# analogue-board.net
KiCad netlist of a schematic drawn in EAGLE
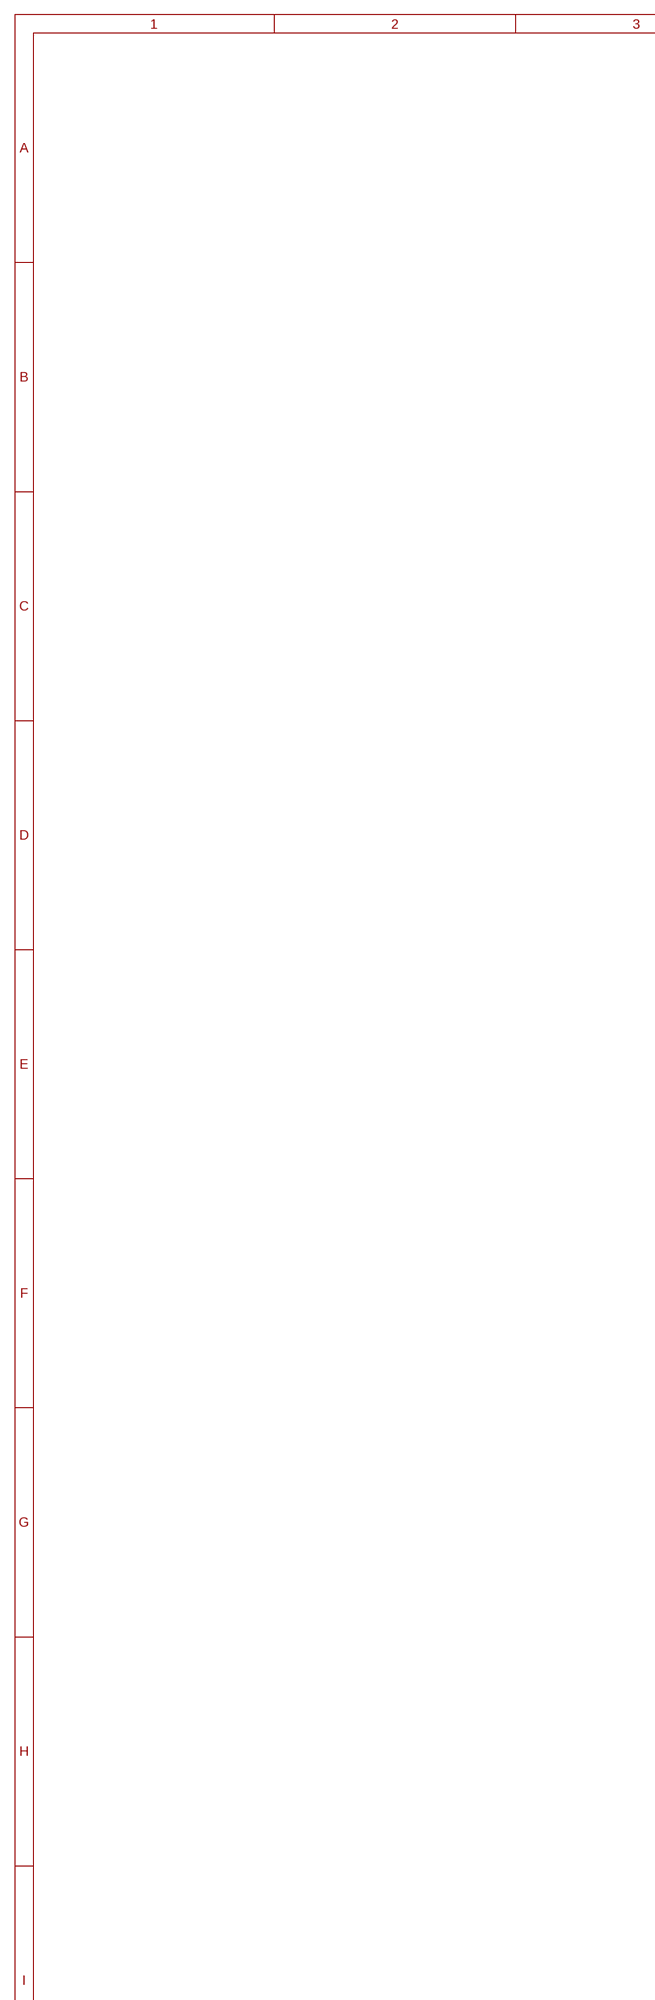
[diagram p0: schematic, sheet 1, part 1 of 2]
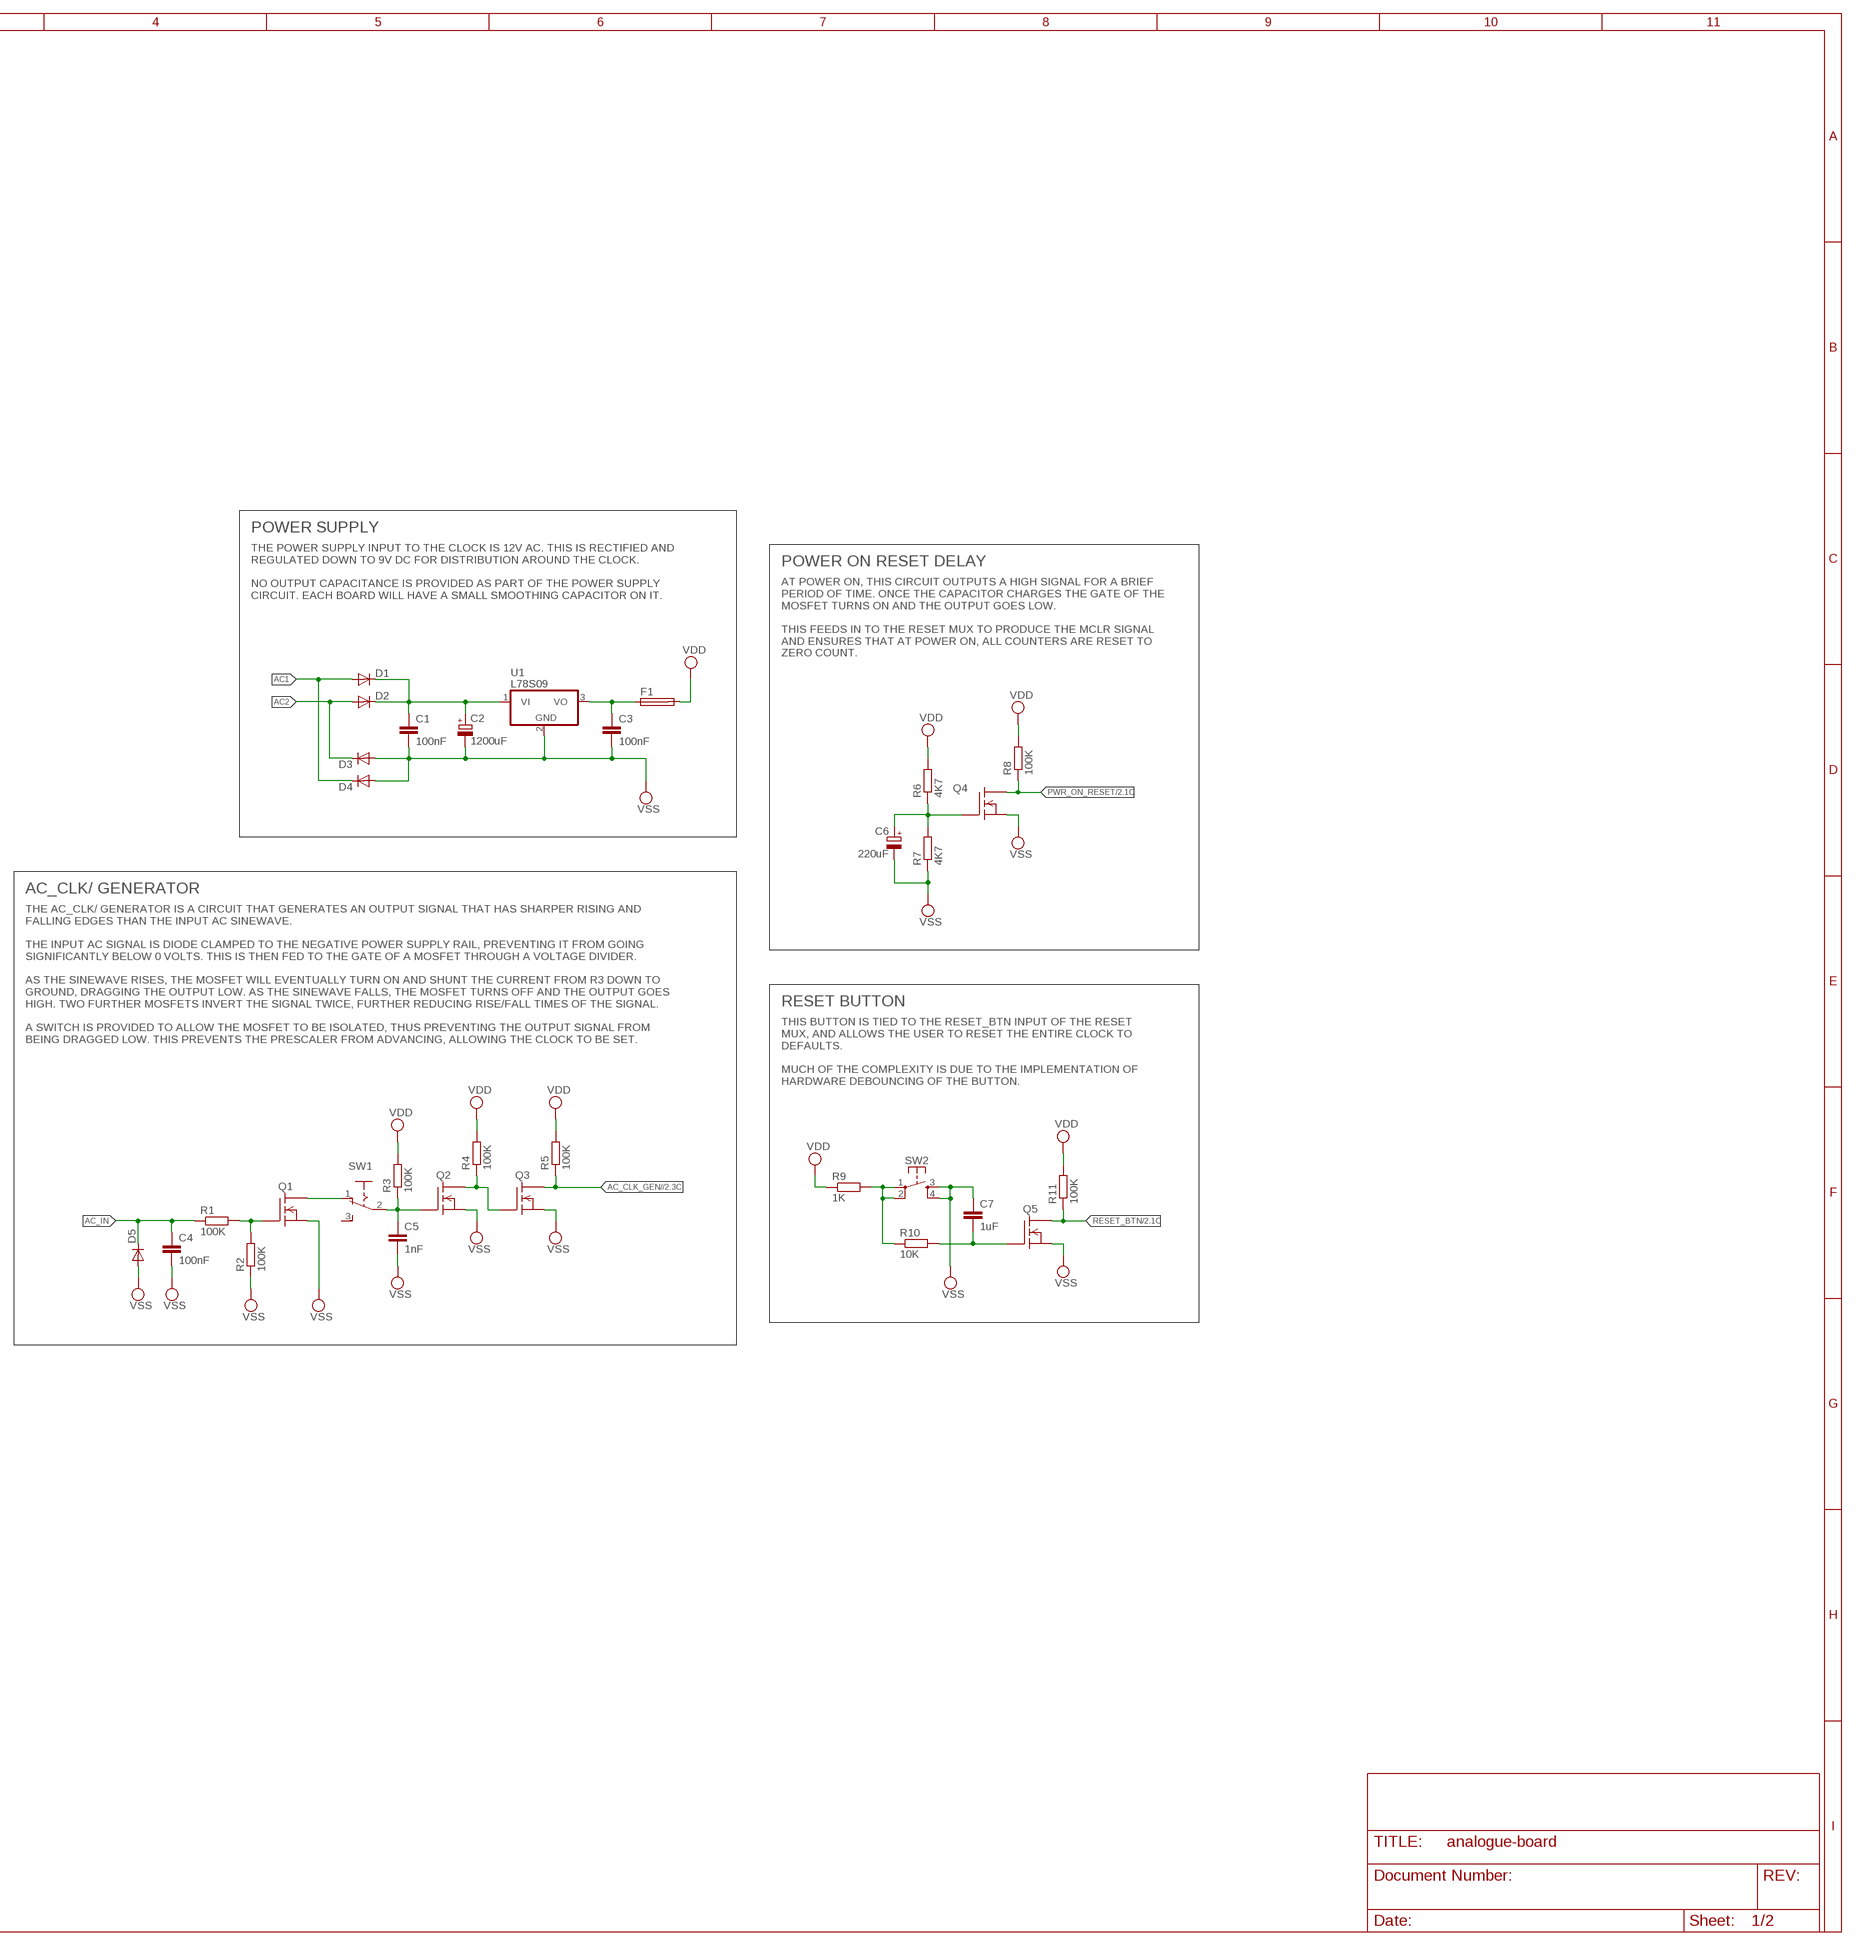
[diagram p1: schematic, sheet 1, part 2 of 2]
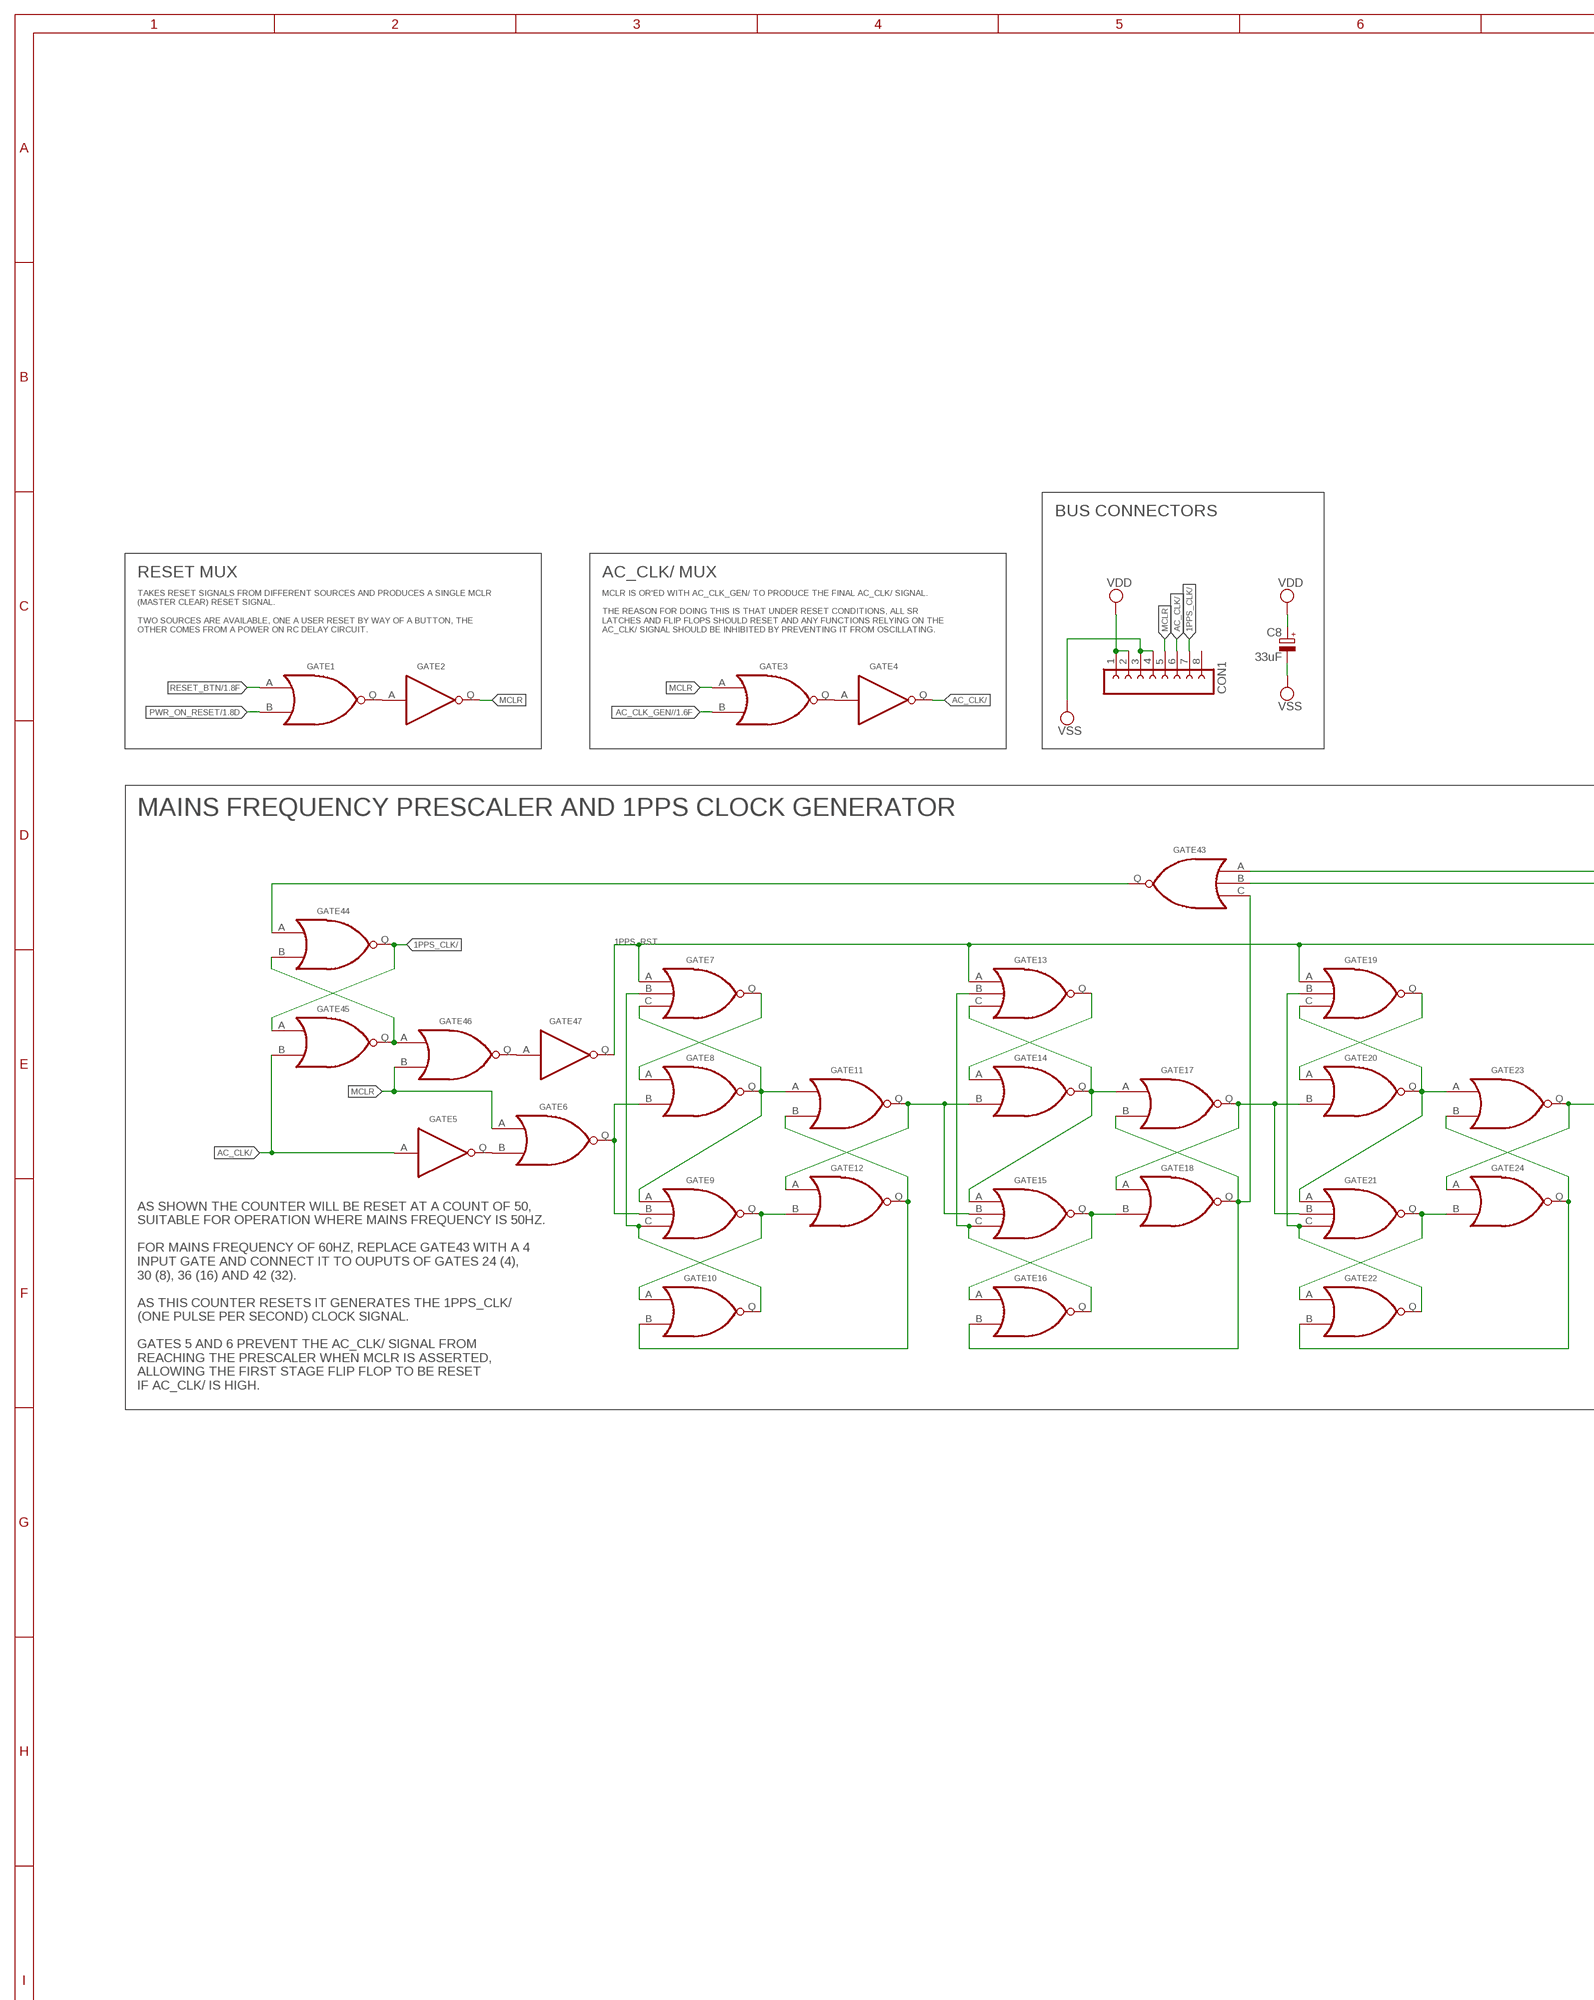
[diagram p2: schematic, sheet 2, part 1 of 2]
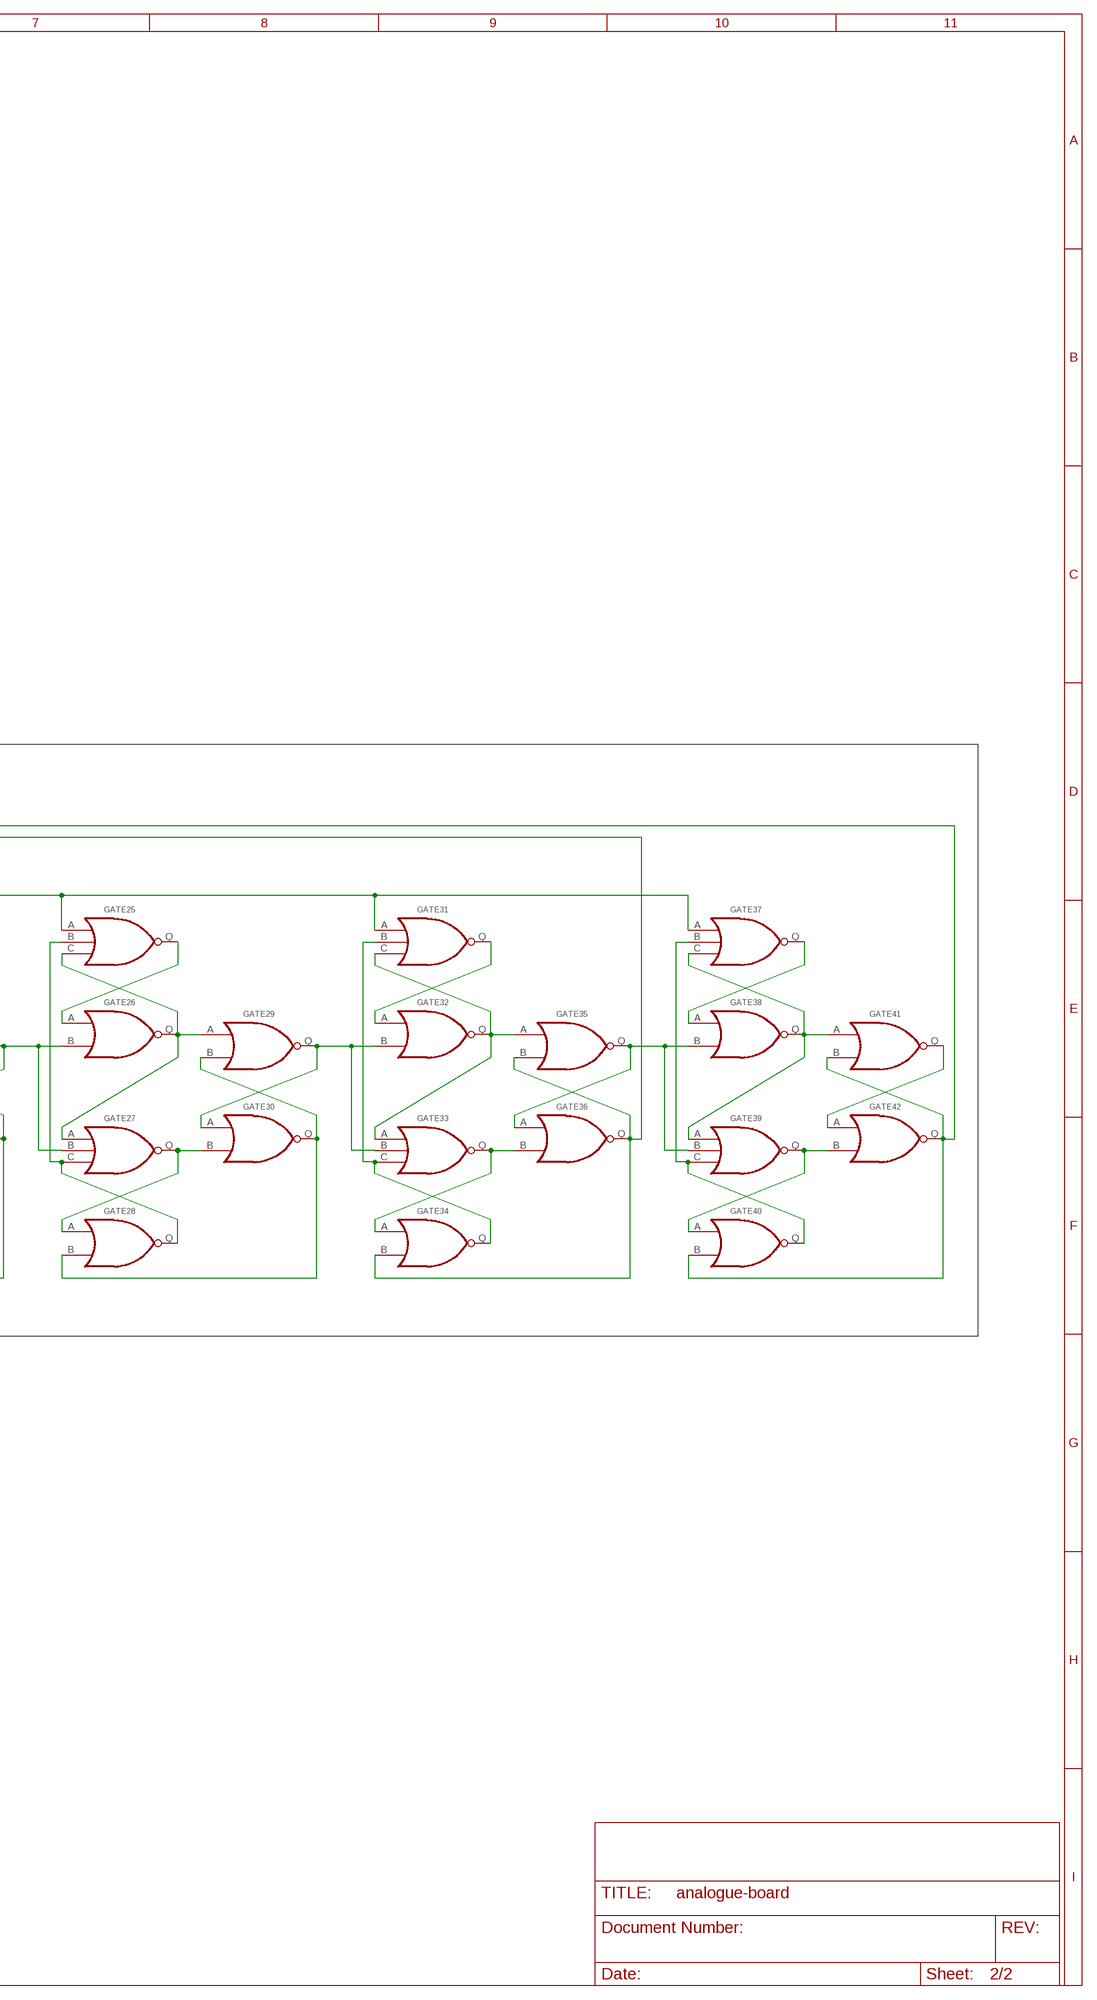
[diagram p3: schematic, sheet 2, part 2 of 2]

(export (version "E")
  (design (tool "Eeschema 10.0.6"))
  (components
    (comp (ref "C1")
      (value "100nF")
      (footprint "eagle-import:C050-024X044")
      (libsource (lib "eagle-import") (part "C-EU050-024X044"))
    )
    (comp (ref "C2")
      (value "1200uF")
      (footprint "eagle-import:E7,5-16")
      (libsource (lib "eagle-import") (part "CPOL-EUE7.5-16"))
    )
    (comp (ref "C3")
      (value "100nF")
      (footprint "eagle-import:C050-024X044")
      (libsource (lib "eagle-import") (part "C-EU050-024X044"))
    )
    (comp (ref "C4")
      (value "100nF")
      (footprint "eagle-import:C050-024X044")
      (libsource (lib "eagle-import") (part "C-EU050-024X044"))
    )
    (comp (ref "C5")
      (value "1nF")
      (footprint "eagle-import:C050-025X075")
      (libsource (lib "eagle-import") (part "C-EU050-025X075"))
    )
    (comp (ref "C6")
      (value "220uF")
      (footprint "eagle-import:E2,5-6")
      (libsource (lib "eagle-import") (part "CPOL-EUE2.5-6"))
    )
    (comp (ref "C7")
      (value "1uF")
      (footprint "eagle-import:C050-025X075")
      (libsource (lib "eagle-import") (part "C-EU050-025X075"))
    )
    (comp (ref "D1")
      (value "1N4004")
      (footprint "eagle-import:DO41-10")
      (libsource (lib "eagle-import") (part "1N4004"))
    )
    (comp (ref "D2")
      (value "1N4004")
      (footprint "eagle-import:DO41-10")
      (libsource (lib "eagle-import") (part "1N4004"))
    )
    (comp (ref "D3")
      (value "1N4004")
      (footprint "eagle-import:DO41-10")
      (libsource (lib "eagle-import") (part "1N4004"))
    )
    (comp (ref "D4")
      (value "1N4004")
      (footprint "eagle-import:DO41-10")
      (libsource (lib "eagle-import") (part "1N4004"))
    )
    (comp (ref "D5")
      (value "1N4004")
      (footprint "eagle-import:DO41-10")
      (libsource (lib "eagle-import") (part "1N4004"))
    )
    (comp (ref "F1")
      (value "TE5")
      (footprint "eagle-import:TE5")
      (libsource (lib "eagle-import") (part "TE5"))
    )
    (comp (ref "Q1")
      (value "2N7000")
      (footprint "eagle-import:TO-92")
      (libsource (lib "eagle-import") (part "2N7000"))
    )
    (comp (ref "Q2")
      (value "2N7000")
      (footprint "eagle-import:TO-92")
      (libsource (lib "eagle-import") (part "2N7000"))
    )
    (comp (ref "Q3")
      (value "2N7000")
      (footprint "eagle-import:TO-92")
      (libsource (lib "eagle-import") (part "2N7000"))
    )
    (comp (ref "Q4")
      (value "2N7000")
      (footprint "eagle-import:TO-92")
      (libsource (lib "eagle-import") (part "2N7000"))
    )
    (comp (ref "Q5")
      (value "2N7000")
      (footprint "eagle-import:TO-92")
      (libsource (lib "eagle-import") (part "2N7000"))
    )
    (comp (ref "R1")
      (value "100K")
      (footprint "eagle-import:0207_2V")
      (libsource (lib "eagle-import") (part "R-EU_0207/2V"))
    )
    (comp (ref "R2")
      (value "100K")
      (footprint "eagle-import:0207_2V")
      (libsource (lib "eagle-import") (part "R-EU_0207/2V"))
    )
    (comp (ref "R3")
      (value "100K")
      (footprint "eagle-import:0207_2V")
      (libsource (lib "eagle-import") (part "R-EU_0207/2V"))
    )
    (comp (ref "R4")
      (value "100K")
      (footprint "eagle-import:0207_2V")
      (libsource (lib "eagle-import") (part "R-EU_0207/2V"))
    )
    (comp (ref "R5")
      (value "100K")
      (footprint "eagle-import:0207_2V")
      (libsource (lib "eagle-import") (part "R-EU_0207/2V"))
    )
    (comp (ref "R6")
      (value "4K7")
      (footprint "eagle-import:0207_2V")
      (libsource (lib "eagle-import") (part "R-EU_0207/2V"))
    )
    (comp (ref "R7")
      (value "4K7")
      (footprint "eagle-import:0207_2V")
      (libsource (lib "eagle-import") (part "R-EU_0207/2V"))
    )
    (comp (ref "R8")
      (value "100K")
      (footprint "eagle-import:0207_2V")
      (libsource (lib "eagle-import") (part "R-EU_0207/2V"))
    )
    (comp (ref "R9")
      (value "1K")
      (footprint "eagle-import:0207_2V")
      (libsource (lib "eagle-import") (part "R-EU_0207/2V"))
    )
    (comp (ref "R10")
      (value "10K")
      (footprint "eagle-import:0207_2V")
      (libsource (lib "eagle-import") (part "R-EU_0207/2V"))
    )
    (comp (ref "R11")
      (value "100K")
      (footprint "eagle-import:0207_2V")
      (libsource (lib "eagle-import") (part "R-EU_0207/2V"))
    )
    (comp (ref "SW1")
      (value "255SB")
      (footprint "eagle-import:255SB")
      (libsource (lib "eagle-import") (part "255SB"))
    )
    (comp (ref "SW2")
      (value "SPST-TACSWITCH")
      (footprint "eagle-import:TE-SMD-TACSWITCH")
      (libsource (lib "eagle-import") (part "SPST-TACSWITCH"))
    )
    (comp (ref "U1")
      (value "L78S09")
      (footprint "eagle-import:TO220H")
      (libsource (lib "eagle-import") (part "78T05"))
    )
    (comp (ref "C8")
      (value "33uF")
      (footprint "eagle-import:E2,5-6")
      (libsource (lib "eagle-import") (part "CPOL-EUE2.5-6"))
    )
    (comp (ref "CON1")
      (value "FE08-1")
      (footprint "eagle-import:FE08")
      (libsource (lib "eagle-import") (part "FE08-1"))
    )
    (comp (ref "GATE1")
      (value "2NOR")
      (footprint "eagle-import:2NOR")
      (libsource (lib "eagle-import") (part "2NOR"))
    )
    (comp (ref "GATE2")
      (value "INVERTER")
      (footprint "eagle-import:INVERTER")
      (libsource (lib "eagle-import") (part "INVERTER"))
    )
    (comp (ref "GATE3")
      (value "2NOR")
      (footprint "eagle-import:2NOR")
      (libsource (lib "eagle-import") (part "2NOR"))
    )
    (comp (ref "GATE4")
      (value "INVERTER")
      (footprint "eagle-import:INVERTER")
      (libsource (lib "eagle-import") (part "INVERTER"))
    )
    (comp (ref "GATE5")
      (value "INVERTER")
      (footprint "eagle-import:INVERTER")
      (libsource (lib "eagle-import") (part "INVERTER"))
    )
    (comp (ref "GATE6")
      (value "2NOR")
      (footprint "eagle-import:2NOR")
      (libsource (lib "eagle-import") (part "2NOR"))
    )
    (comp (ref "GATE7")
      (value "3NOR")
      (footprint "eagle-import:3NOR")
      (libsource (lib "eagle-import") (part "3NOR"))
    )
    (comp (ref "GATE8")
      (value "2NOR")
      (footprint "eagle-import:2NOR")
      (libsource (lib "eagle-import") (part "2NOR"))
    )
    (comp (ref "GATE9")
      (value "3NOR")
      (footprint "eagle-import:3NOR")
      (libsource (lib "eagle-import") (part "3NOR"))
    )
    (comp (ref "GATE10")
      (value "2NOR")
      (footprint "eagle-import:2NOR")
      (libsource (lib "eagle-import") (part "2NOR"))
    )
    (comp (ref "GATE11")
      (value "2NOR")
      (footprint "eagle-import:2NOR")
      (libsource (lib "eagle-import") (part "2NOR"))
    )
    (comp (ref "GATE12")
      (value "2NOR")
      (footprint "eagle-import:2NOR")
      (libsource (lib "eagle-import") (part "2NOR"))
    )
    (comp (ref "GATE13")
      (value "3NOR")
      (footprint "eagle-import:3NOR")
      (libsource (lib "eagle-import") (part "3NOR"))
    )
    (comp (ref "GATE14")
      (value "2NOR")
      (footprint "eagle-import:2NOR")
      (libsource (lib "eagle-import") (part "2NOR"))
    )
    (comp (ref "GATE15")
      (value "3NOR")
      (footprint "eagle-import:3NOR")
      (libsource (lib "eagle-import") (part "3NOR"))
    )
    (comp (ref "GATE16")
      (value "2NOR")
      (footprint "eagle-import:2NOR")
      (libsource (lib "eagle-import") (part "2NOR"))
    )
    (comp (ref "GATE17")
      (value "2NOR")
      (footprint "eagle-import:2NOR")
      (libsource (lib "eagle-import") (part "2NOR"))
    )
    (comp (ref "GATE18")
      (value "2NOR")
      (footprint "eagle-import:2NOR")
      (libsource (lib "eagle-import") (part "2NOR"))
    )
    (comp (ref "GATE19")
      (value "3NOR")
      (footprint "eagle-import:3NOR")
      (libsource (lib "eagle-import") (part "3NOR"))
    )
    (comp (ref "GATE20")
      (value "2NOR")
      (footprint "eagle-import:2NOR")
      (libsource (lib "eagle-import") (part "2NOR"))
    )
    (comp (ref "GATE21")
      (value "3NOR")
      (footprint "eagle-import:3NOR")
      (libsource (lib "eagle-import") (part "3NOR"))
    )
    (comp (ref "GATE22")
      (value "2NOR")
      (footprint "eagle-import:2NOR")
      (libsource (lib "eagle-import") (part "2NOR"))
    )
    (comp (ref "GATE23")
      (value "2NOR")
      (footprint "eagle-import:2NOR")
      (libsource (lib "eagle-import") (part "2NOR"))
    )
    (comp (ref "GATE24")
      (value "2NOR")
      (footprint "eagle-import:2NOR")
      (libsource (lib "eagle-import") (part "2NOR"))
    )
    (comp (ref "GATE25")
      (value "3NOR")
      (footprint "eagle-import:3NOR")
      (libsource (lib "eagle-import") (part "3NOR"))
    )
    (comp (ref "GATE26")
      (value "2NOR")
      (footprint "eagle-import:2NOR")
      (libsource (lib "eagle-import") (part "2NOR"))
    )
    (comp (ref "GATE27")
      (value "3NOR")
      (footprint "eagle-import:3NOR")
      (libsource (lib "eagle-import") (part "3NOR"))
    )
    (comp (ref "GATE28")
      (value "2NOR")
      (footprint "eagle-import:2NOR")
      (libsource (lib "eagle-import") (part "2NOR"))
    )
    (comp (ref "GATE29")
      (value "2NOR")
      (footprint "eagle-import:2NOR")
      (libsource (lib "eagle-import") (part "2NOR"))
    )
    (comp (ref "GATE30")
      (value "2NOR")
      (footprint "eagle-import:2NOR")
      (libsource (lib "eagle-import") (part "2NOR"))
    )
    (comp (ref "GATE31")
      (value "3NOR")
      (footprint "eagle-import:3NOR")
      (libsource (lib "eagle-import") (part "3NOR"))
    )
    (comp (ref "GATE32")
      (value "2NOR")
      (footprint "eagle-import:2NOR")
      (libsource (lib "eagle-import") (part "2NOR"))
    )
    (comp (ref "GATE33")
      (value "3NOR")
      (footprint "eagle-import:3NOR")
      (libsource (lib "eagle-import") (part "3NOR"))
    )
    (comp (ref "GATE34")
      (value "2NOR")
      (footprint "eagle-import:2NOR")
      (libsource (lib "eagle-import") (part "2NOR"))
    )
    (comp (ref "GATE35")
      (value "2NOR")
      (footprint "eagle-import:2NOR")
      (libsource (lib "eagle-import") (part "2NOR"))
    )
    (comp (ref "GATE36")
      (value "2NOR")
      (footprint "eagle-import:2NOR")
      (libsource (lib "eagle-import") (part "2NOR"))
    )
    (comp (ref "GATE37")
      (value "3NOR")
      (footprint "eagle-import:3NOR")
      (libsource (lib "eagle-import") (part "3NOR"))
    )
    (comp (ref "GATE38")
      (value "2NOR")
      (footprint "eagle-import:2NOR")
      (libsource (lib "eagle-import") (part "2NOR"))
    )
    (comp (ref "GATE39")
      (value "3NOR")
      (footprint "eagle-import:3NOR")
      (libsource (lib "eagle-import") (part "3NOR"))
    )
    (comp (ref "GATE40")
      (value "2NOR")
      (footprint "eagle-import:2NOR")
      (libsource (lib "eagle-import") (part "2NOR"))
    )
    (comp (ref "GATE41")
      (value "2NOR")
      (footprint "eagle-import:2NOR")
      (libsource (lib "eagle-import") (part "2NOR"))
    )
    (comp (ref "GATE42")
      (value "2NOR")
      (footprint "eagle-import:2NOR")
      (libsource (lib "eagle-import") (part "2NOR"))
    )
    (comp (ref "GATE43")
      (value "3NOR")
      (footprint "eagle-import:3NOR")
      (libsource (lib "eagle-import") (part "3NOR"))
    )
    (comp (ref "GATE44")
      (value "2NOR")
      (footprint "eagle-import:2NOR")
      (libsource (lib "eagle-import") (part "2NOR"))
    )
    (comp (ref "GATE45")
      (value "2NOR")
      (footprint "eagle-import:2NOR")
      (libsource (lib "eagle-import") (part "2NOR"))
    )
    (comp (ref "GATE46")
      (value "2NOR")
      (footprint "eagle-import:2NOR")
      (libsource (lib "eagle-import") (part "2NOR"))
    )
    (comp (ref "GATE47")
      (value "INVERTER")
      (footprint "eagle-import:INVERTER")
      (libsource (lib "eagle-import") (part "INVERTER"))
    )
  )
  (nets
    (net (code "1") (name "1PPS_CLK{slash}") (class "Default")
      (node (ref "CON1") (pin "7") (pinfunction "7_7") (pintype "passive"))
      (node (ref "GATE44") (pin "Q") (pinfunction "Q_Q") (pintype "output"))
      (node (ref "GATE45") (pin "A") (pinfunction "A_A") (pintype "input"))
    )
    (net (code "2") (name "1PPS_RST") (class "Default")
      (node (ref "GATE13") (pin "A") (pinfunction "A_A") (pintype "input"))
      (node (ref "GATE19") (pin "A") (pinfunction "A_A") (pintype "input"))
      (node (ref "GATE25") (pin "A") (pinfunction "A_A") (pintype "input"))
      (node (ref "GATE31") (pin "A") (pinfunction "A_A") (pintype "input"))
      (node (ref "GATE37") (pin "A") (pinfunction "A_A") (pintype "input"))
      (node (ref "GATE47") (pin "Q") (pinfunction "Q_Q") (pintype "output"))
      (node (ref "GATE7") (pin "A") (pinfunction "A_A") (pintype "input"))
    )
    (net (code "3") (name "AC1") (class "Default")
      (node (ref "D1") (pin "A") (pinfunction "A_A") (pintype "passive"))
      (node (ref "D4") (pin "C") (pinfunction "C_C") (pintype "passive"))
    )
    (net (code "4") (name "AC2") (class "Default")
      (node (ref "D2") (pin "A") (pinfunction "A_A") (pintype "passive"))
      (node (ref "D3") (pin "C") (pinfunction "C_C") (pintype "passive"))
    )
    (net (code "5") (name "AC_CLK_GEN{slash}") (class "Default")
      (node (ref "GATE3") (pin "B") (pinfunction "B_B") (pintype "input"))
      (node (ref "Q3") (pin "3") (pinfunction "D_3") (pintype "passive"))
      (node (ref "R5") (pin "1") (pinfunction "1_1") (pintype "passive"))
    )
    (net (code "6") (name "AC_CLK{slash}") (class "Default")
      (node (ref "CON1") (pin "6") (pinfunction "6_6") (pintype "passive"))
      (node (ref "GATE4") (pin "Q") (pinfunction "Q_Q") (pintype "output"))
      (node (ref "GATE45") (pin "B") (pinfunction "B_B") (pintype "input"))
      (node (ref "GATE5") (pin "A") (pinfunction "A_A") (pintype "input"))
    )
    (net (code "7") (name "AC_IN") (class "Default")
      (node (ref "C4") (pin "1") (pinfunction "1_1") (pintype "passive"))
      (node (ref "D5") (pin "C") (pinfunction "C_C") (pintype "passive"))
      (node (ref "R1") (pin "1") (pinfunction "1_1") (pintype "passive"))
    )
    (net (code "8") (name "MCLR") (class "Default")
      (node (ref "CON1") (pin "5") (pinfunction "5_5") (pintype "passive"))
      (node (ref "GATE2") (pin "Q") (pinfunction "Q_Q") (pintype "output"))
      (node (ref "GATE3") (pin "A") (pinfunction "A_A") (pintype "input"))
      (node (ref "GATE46") (pin "B") (pinfunction "B_B") (pintype "input"))
      (node (ref "GATE6") (pin "A") (pinfunction "A_A") (pintype "input"))
    )
    (net (code "9") (name "Net-(GATE1-PadQ)") (class "Default")
      (node (ref "GATE1") (pin "Q") (pinfunction "Q_Q") (pintype "output"))
      (node (ref "GATE2") (pin "A") (pinfunction "A_A") (pintype "input"))
    )
    (net (code "10") (name "Net-(GATE3-PadQ)") (class "Default")
      (node (ref "GATE3") (pin "Q") (pinfunction "Q_Q") (pintype "output"))
      (node (ref "GATE4") (pin "A") (pinfunction "A_A") (pintype "input"))
    )
    (net (code "11") (name "Net-(GATE5-PadQ)") (class "Default")
      (node (ref "GATE5") (pin "Q") (pinfunction "Q_Q") (pintype "output"))
      (node (ref "GATE6") (pin "B") (pinfunction "B_B") (pintype "input"))
    )
    (net (code "12") (name "Net-(GATE6-PadQ)") (class "Default")
      (node (ref "GATE6") (pin "Q") (pinfunction "Q_Q") (pintype "output"))
      (node (ref "GATE8") (pin "B") (pinfunction "B_B") (pintype "input"))
      (node (ref "GATE9") (pin "B") (pinfunction "B_B") (pintype "input"))
    )
    (net (code "13") (name "Net-(GATE7-PadQ)") (class "Default")
      (node (ref "GATE7") (pin "Q") (pinfunction "Q_Q") (pintype "output"))
      (node (ref "GATE8") (pin "A") (pinfunction "A_A") (pintype "input"))
    )
    (net (code "14") (name "Net-(GATE10-PadA)") (class "Default")
      (node (ref "GATE10") (pin "A") (pinfunction "A_A") (pintype "input"))
      (node (ref "GATE12") (pin "B") (pinfunction "B_B") (pintype "input"))
      (node (ref "GATE9") (pin "Q") (pinfunction "Q_Q") (pintype "output"))
    )
    (net (code "15") (name "Net-(GATE10-PadB)") (class "Default")
      (node (ref "GATE10") (pin "B") (pinfunction "B_B") (pintype "input"))
      (node (ref "GATE11") (pin "B") (pinfunction "B_B") (pintype "input"))
      (node (ref "GATE12") (pin "Q") (pinfunction "Q_Q") (pintype "output"))
    )
    (net (code "16") (name "Net-(GATE10-PadQ)") (class "Default")
      (node (ref "GATE10") (pin "Q") (pinfunction "Q_Q") (pintype "output"))
      (node (ref "GATE7") (pin "B") (pinfunction "B_B") (pintype "input"))
      (node (ref "GATE9") (pin "C") (pinfunction "C_C") (pintype "input"))
    )
    (net (code "17") (name "Net-(GATE11-PadA)") (class "Default")
      (node (ref "GATE11") (pin "A") (pinfunction "A_A") (pintype "input"))
      (node (ref "GATE7") (pin "C") (pinfunction "C_C") (pintype "input"))
      (node (ref "GATE8") (pin "Q") (pinfunction "Q_Q") (pintype "output"))
      (node (ref "GATE9") (pin "A") (pinfunction "A_A") (pintype "input"))
    )
    (net (code "18") (name "Net-(GATE11-PadQ)") (class "Default")
      (node (ref "GATE11") (pin "Q") (pinfunction "Q_Q") (pintype "output"))
      (node (ref "GATE12") (pin "A") (pinfunction "A_A") (pintype "input"))
      (node (ref "GATE14") (pin "B") (pinfunction "B_B") (pintype "input"))
      (node (ref "GATE15") (pin "B") (pinfunction "B_B") (pintype "input"))
    )
    (net (code "19") (name "Net-(GATE13-PadB)") (class "Default")
      (node (ref "GATE13") (pin "B") (pinfunction "B_B") (pintype "input"))
      (node (ref "GATE15") (pin "C") (pinfunction "C_C") (pintype "input"))
      (node (ref "GATE16") (pin "Q") (pinfunction "Q_Q") (pintype "output"))
    )
    (net (code "20") (name "Net-(GATE13-PadC)") (class "Default")
      (node (ref "GATE13") (pin "C") (pinfunction "C_C") (pintype "input"))
      (node (ref "GATE14") (pin "Q") (pinfunction "Q_Q") (pintype "output"))
      (node (ref "GATE15") (pin "A") (pinfunction "A_A") (pintype "input"))
      (node (ref "GATE17") (pin "A") (pinfunction "A_A") (pintype "input"))
    )
    (net (code "21") (name "Net-(GATE13-PadQ)") (class "Default")
      (node (ref "GATE13") (pin "Q") (pinfunction "Q_Q") (pintype "output"))
      (node (ref "GATE14") (pin "A") (pinfunction "A_A") (pintype "input"))
    )
    (net (code "22") (name "Net-(GATE15-PadQ)") (class "Default")
      (node (ref "GATE15") (pin "Q") (pinfunction "Q_Q") (pintype "output"))
      (node (ref "GATE16") (pin "A") (pinfunction "A_A") (pintype "input"))
      (node (ref "GATE18") (pin "B") (pinfunction "B_B") (pintype "input"))
    )
    (net (code "23") (name "Net-(GATE16-PadB)") (class "Default")
      (node (ref "GATE16") (pin "B") (pinfunction "B_B") (pintype "input"))
      (node (ref "GATE17") (pin "B") (pinfunction "B_B") (pintype "input"))
      (node (ref "GATE18") (pin "Q") (pinfunction "Q_Q") (pintype "output"))
      (node (ref "GATE43") (pin "C") (pinfunction "C_C") (pintype "input"))
    )
    (net (code "24") (name "Net-(GATE17-PadQ)") (class "Default")
      (node (ref "GATE17") (pin "Q") (pinfunction "Q_Q") (pintype "output"))
      (node (ref "GATE18") (pin "A") (pinfunction "A_A") (pintype "input"))
      (node (ref "GATE20") (pin "B") (pinfunction "B_B") (pintype "input"))
      (node (ref "GATE21") (pin "B") (pinfunction "B_B") (pintype "input"))
    )
    (net (code "25") (name "Net-(GATE19-PadB)") (class "Default")
      (node (ref "GATE19") (pin "B") (pinfunction "B_B") (pintype "input"))
      (node (ref "GATE21") (pin "C") (pinfunction "C_C") (pintype "input"))
      (node (ref "GATE22") (pin "Q") (pinfunction "Q_Q") (pintype "output"))
    )
    (net (code "26") (name "Net-(GATE19-PadC)") (class "Default")
      (node (ref "GATE19") (pin "C") (pinfunction "C_C") (pintype "input"))
      (node (ref "GATE20") (pin "Q") (pinfunction "Q_Q") (pintype "output"))
      (node (ref "GATE21") (pin "A") (pinfunction "A_A") (pintype "input"))
      (node (ref "GATE23") (pin "A") (pinfunction "A_A") (pintype "input"))
    )
    (net (code "27") (name "Net-(GATE19-PadQ)") (class "Default")
      (node (ref "GATE19") (pin "Q") (pinfunction "Q_Q") (pintype "output"))
      (node (ref "GATE20") (pin "A") (pinfunction "A_A") (pintype "input"))
    )
    (net (code "28") (name "Net-(GATE21-PadQ)") (class "Default")
      (node (ref "GATE21") (pin "Q") (pinfunction "Q_Q") (pintype "output"))
      (node (ref "GATE22") (pin "A") (pinfunction "A_A") (pintype "input"))
      (node (ref "GATE24") (pin "B") (pinfunction "B_B") (pintype "input"))
    )
    (net (code "29") (name "Net-(GATE22-PadB)") (class "Default")
      (node (ref "GATE22") (pin "B") (pinfunction "B_B") (pintype "input"))
      (node (ref "GATE23") (pin "B") (pinfunction "B_B") (pintype "input"))
      (node (ref "GATE24") (pin "Q") (pinfunction "Q_Q") (pintype "output"))
    )
    (net (code "30") (name "Net-(GATE23-PadQ)") (class "Default")
      (node (ref "GATE23") (pin "Q") (pinfunction "Q_Q") (pintype "output"))
      (node (ref "GATE24") (pin "A") (pinfunction "A_A") (pintype "input"))
      (node (ref "GATE26") (pin "B") (pinfunction "B_B") (pintype "input"))
      (node (ref "GATE27") (pin "B") (pinfunction "B_B") (pintype "input"))
    )
    (net (code "31") (name "Net-(GATE25-PadB)") (class "Default")
      (node (ref "GATE25") (pin "B") (pinfunction "B_B") (pintype "input"))
      (node (ref "GATE27") (pin "C") (pinfunction "C_C") (pintype "input"))
      (node (ref "GATE28") (pin "Q") (pinfunction "Q_Q") (pintype "output"))
    )
    (net (code "32") (name "Net-(GATE25-PadC)") (class "Default")
      (node (ref "GATE25") (pin "C") (pinfunction "C_C") (pintype "input"))
      (node (ref "GATE26") (pin "Q") (pinfunction "Q_Q") (pintype "output"))
      (node (ref "GATE27") (pin "A") (pinfunction "A_A") (pintype "input"))
      (node (ref "GATE29") (pin "A") (pinfunction "A_A") (pintype "input"))
    )
    (net (code "33") (name "Net-(GATE25-PadQ)") (class "Default")
      (node (ref "GATE25") (pin "Q") (pinfunction "Q_Q") (pintype "output"))
      (node (ref "GATE26") (pin "A") (pinfunction "A_A") (pintype "input"))
    )
    (net (code "34") (name "Net-(GATE27-PadQ)") (class "Default")
      (node (ref "GATE27") (pin "Q") (pinfunction "Q_Q") (pintype "output"))
      (node (ref "GATE28") (pin "A") (pinfunction "A_A") (pintype "input"))
      (node (ref "GATE30") (pin "B") (pinfunction "B_B") (pintype "input"))
    )
    (net (code "35") (name "Net-(GATE28-PadB)") (class "Default")
      (node (ref "GATE28") (pin "B") (pinfunction "B_B") (pintype "input"))
      (node (ref "GATE29") (pin "B") (pinfunction "B_B") (pintype "input"))
      (node (ref "GATE30") (pin "Q") (pinfunction "Q_Q") (pintype "output"))
    )
    (net (code "36") (name "Net-(GATE29-PadQ)") (class "Default")
      (node (ref "GATE29") (pin "Q") (pinfunction "Q_Q") (pintype "output"))
      (node (ref "GATE30") (pin "A") (pinfunction "A_A") (pintype "input"))
      (node (ref "GATE32") (pin "B") (pinfunction "B_B") (pintype "input"))
      (node (ref "GATE33") (pin "B") (pinfunction "B_B") (pintype "input"))
    )
    (net (code "37") (name "Net-(GATE31-PadB)") (class "Default")
      (node (ref "GATE31") (pin "B") (pinfunction "B_B") (pintype "input"))
      (node (ref "GATE33") (pin "C") (pinfunction "C_C") (pintype "input"))
      (node (ref "GATE34") (pin "Q") (pinfunction "Q_Q") (pintype "output"))
    )
    (net (code "38") (name "Net-(GATE31-PadC)") (class "Default")
      (node (ref "GATE31") (pin "C") (pinfunction "C_C") (pintype "input"))
      (node (ref "GATE32") (pin "Q") (pinfunction "Q_Q") (pintype "output"))
      (node (ref "GATE33") (pin "A") (pinfunction "A_A") (pintype "input"))
      (node (ref "GATE35") (pin "A") (pinfunction "A_A") (pintype "input"))
    )
    (net (code "39") (name "Net-(GATE31-PadQ)") (class "Default")
      (node (ref "GATE31") (pin "Q") (pinfunction "Q_Q") (pintype "output"))
      (node (ref "GATE32") (pin "A") (pinfunction "A_A") (pintype "input"))
    )
    (net (code "40") (name "Net-(GATE33-PadQ)") (class "Default")
      (node (ref "GATE33") (pin "Q") (pinfunction "Q_Q") (pintype "output"))
      (node (ref "GATE34") (pin "A") (pinfunction "A_A") (pintype "input"))
      (node (ref "GATE36") (pin "B") (pinfunction "B_B") (pintype "input"))
    )
    (net (code "41") (name "Net-(GATE34-PadB)") (class "Default")
      (node (ref "GATE34") (pin "B") (pinfunction "B_B") (pintype "input"))
      (node (ref "GATE35") (pin "B") (pinfunction "B_B") (pintype "input"))
      (node (ref "GATE36") (pin "Q") (pinfunction "Q_Q") (pintype "output"))
      (node (ref "GATE43") (pin "B") (pinfunction "B_B") (pintype "input"))
    )
    (net (code "42") (name "Net-(GATE35-PadQ)") (class "Default")
      (node (ref "GATE35") (pin "Q") (pinfunction "Q_Q") (pintype "output"))
      (node (ref "GATE36") (pin "A") (pinfunction "A_A") (pintype "input"))
      (node (ref "GATE38") (pin "B") (pinfunction "B_B") (pintype "input"))
      (node (ref "GATE39") (pin "B") (pinfunction "B_B") (pintype "input"))
    )
    (net (code "43") (name "Net-(GATE37-PadB)") (class "Default")
      (node (ref "GATE37") (pin "B") (pinfunction "B_B") (pintype "input"))
      (node (ref "GATE39") (pin "C") (pinfunction "C_C") (pintype "input"))
      (node (ref "GATE40") (pin "Q") (pinfunction "Q_Q") (pintype "output"))
    )
    (net (code "44") (name "Net-(GATE37-PadC)") (class "Default")
      (node (ref "GATE37") (pin "C") (pinfunction "C_C") (pintype "input"))
      (node (ref "GATE38") (pin "Q") (pinfunction "Q_Q") (pintype "output"))
      (node (ref "GATE39") (pin "A") (pinfunction "A_A") (pintype "input"))
      (node (ref "GATE41") (pin "A") (pinfunction "A_A") (pintype "input"))
    )
    (net (code "45") (name "Net-(GATE37-PadQ)") (class "Default")
      (node (ref "GATE37") (pin "Q") (pinfunction "Q_Q") (pintype "output"))
      (node (ref "GATE38") (pin "A") (pinfunction "A_A") (pintype "input"))
    )
    (net (code "46") (name "Net-(GATE39-PadQ)") (class "Default")
      (node (ref "GATE39") (pin "Q") (pinfunction "Q_Q") (pintype "output"))
      (node (ref "GATE40") (pin "A") (pinfunction "A_A") (pintype "input"))
      (node (ref "GATE42") (pin "B") (pinfunction "B_B") (pintype "input"))
    )
    (net (code "47") (name "Net-(GATE40-PadB)") (class "Default")
      (node (ref "GATE40") (pin "B") (pinfunction "B_B") (pintype "input"))
      (node (ref "GATE41") (pin "B") (pinfunction "B_B") (pintype "input"))
      (node (ref "GATE42") (pin "Q") (pinfunction "Q_Q") (pintype "output"))
      (node (ref "GATE43") (pin "A") (pinfunction "A_A") (pintype "input"))
    )
    (net (code "48") (name "Net-(GATE41-PadQ)") (class "Default")
      (node (ref "GATE41") (pin "Q") (pinfunction "Q_Q") (pintype "output"))
      (node (ref "GATE42") (pin "A") (pinfunction "A_A") (pintype "input"))
    )
    (net (code "49") (name "Net-(GATE43-PadQ)") (class "Default")
      (node (ref "GATE43") (pin "Q") (pinfunction "Q_Q") (pintype "output"))
      (node (ref "GATE44") (pin "A") (pinfunction "A_A") (pintype "input"))
    )
    (net (code "50") (name "Net-(GATE44-PadB)") (class "Default")
      (node (ref "GATE44") (pin "B") (pinfunction "B_B") (pintype "input"))
      (node (ref "GATE45") (pin "Q") (pinfunction "Q_Q") (pintype "output"))
      (node (ref "GATE46") (pin "A") (pinfunction "A_A") (pintype "input"))
    )
    (net (code "51") (name "Net-(GATE46-PadQ)") (class "Default")
      (node (ref "GATE46") (pin "Q") (pinfunction "Q_Q") (pintype "output"))
      (node (ref "GATE47") (pin "A") (pinfunction "A_A") (pintype "input"))
    )
    (net (code "52") (name "Net-(Q1-D)") (class "Default")
      (node (ref "Q1") (pin "3") (pinfunction "D_3") (pintype "passive"))
      (node (ref "SW1") (pin "1") (pinfunction "O_1") (pintype "passive"))
    )
    (net (code "53") (name "Net-(Q1-G)") (class "Default")
      (node (ref "Q1") (pin "2") (pinfunction "G_2") (pintype "passive"))
      (node (ref "R1") (pin "2") (pinfunction "2_2") (pintype "passive"))
      (node (ref "R2") (pin "2") (pinfunction "2_2") (pintype "passive"))
    )
    (net (code "54") (name "Net-(Q2-D)") (class "Default")
      (node (ref "Q2") (pin "3") (pinfunction "D_3") (pintype "passive"))
      (node (ref "Q3") (pin "2") (pinfunction "G_2") (pintype "passive"))
      (node (ref "R4") (pin "1") (pinfunction "1_1") (pintype "passive"))
    )
    (net (code "55") (name "Net-(Q2-G)") (class "Default")
      (node (ref "C5") (pin "1") (pinfunction "1_1") (pintype "passive"))
      (node (ref "Q2") (pin "2") (pinfunction "G_2") (pintype "passive"))
      (node (ref "R3") (pin "1") (pinfunction "1_1") (pintype "passive"))
      (node (ref "SW1") (pin "2") (pinfunction "P_2") (pintype "passive"))
    )
    (net (code "56") (name "Net-(Q4-G)") (class "Default")
      (node (ref "C6") (pin "+") (pinfunction "+_+") (pintype "passive"))
      (node (ref "Q4") (pin "2") (pinfunction "G_2") (pintype "passive"))
      (node (ref "R6") (pin "1") (pinfunction "1_1") (pintype "passive"))
      (node (ref "R7") (pin "2") (pinfunction "2_2") (pintype "passive"))
    )
    (net (code "57") (name "Net-(Q5-G)") (class "Default")
      (node (ref "C7") (pin "2") (pinfunction "2_2") (pintype "passive"))
      (node (ref "Q5") (pin "2") (pinfunction "G_2") (pintype "passive"))
      (node (ref "R10") (pin "2") (pinfunction "2_2") (pintype "passive"))
    )
    (net (code "58") (name "Net-(R10-Pad1)") (class "Default")
      (node (ref "R10") (pin "1") (pinfunction "1_1") (pintype "passive"))
      (node (ref "R9") (pin "2") (pinfunction "2_2") (pintype "passive"))
      (node (ref "SW2") (pin "1") (pinfunction "1_1") (pintype "passive"))
      (node (ref "SW2") (pin "2") (pinfunction "2_2") (pintype "passive"))
    )
    (net (code "59") (name "Net-(U1-VI)") (class "Default")
      (node (ref "C1") (pin "1") (pinfunction "1_1") (pintype "passive"))
      (node (ref "C2") (pin "+") (pinfunction "+_+") (pintype "passive"))
      (node (ref "D1") (pin "C") (pinfunction "C_C") (pintype "passive"))
      (node (ref "D2") (pin "C") (pinfunction "C_C") (pintype "passive"))
      (node (ref "U1") (pin "1") (pinfunction "VI_1") (pintype "input"))
    )
    (net (code "60") (name "Net-(U1-VO)") (class "Default")
      (node (ref "C3") (pin "1") (pinfunction "1_1") (pintype "passive"))
      (node (ref "F1") (pin "1") (pinfunction "1_1") (pintype "passive"))
      (node (ref "U1") (pin "3") (pinfunction "VO_3") (pintype "passive"))
    )
    (net (code "61") (name "PWR_ON_RESET") (class "Default")
      (node (ref "GATE1") (pin "B") (pinfunction "B_B") (pintype "input"))
      (node (ref "Q4") (pin "3") (pinfunction "D_3") (pintype "passive"))
      (node (ref "R8") (pin "1") (pinfunction "1_1") (pintype "passive"))
    )
    (net (code "62") (name "RESET_BTN") (class "Default")
      (node (ref "GATE1") (pin "A") (pinfunction "A_A") (pintype "input"))
      (node (ref "Q5") (pin "3") (pinfunction "D_3") (pintype "passive"))
      (node (ref "R11") (pin "1") (pinfunction "1_1") (pintype "passive"))
    )
    (net (code "63") (name "VDD") (class "Default")
      (node (ref "C8") (pin "+") (pinfunction "+_+") (pintype "passive"))
      (node (ref "CON1") (pin "1") (pinfunction "1_1") (pintype "passive"))
      (node (ref "CON1") (pin "2") (pinfunction "2_2") (pintype "passive"))
      (node (ref "F1") (pin "2") (pinfunction "2_2") (pintype "passive"))
      (node (ref "R11") (pin "2") (pinfunction "2_2") (pintype "passive"))
      (node (ref "R3") (pin "2") (pinfunction "2_2") (pintype "passive"))
      (node (ref "R4") (pin "2") (pinfunction "2_2") (pintype "passive"))
      (node (ref "R5") (pin "2") (pinfunction "2_2") (pintype "passive"))
      (node (ref "R6") (pin "2") (pinfunction "2_2") (pintype "passive"))
      (node (ref "R8") (pin "2") (pinfunction "2_2") (pintype "passive"))
      (node (ref "R9") (pin "1") (pinfunction "1_1") (pintype "passive"))
    )
    (net (code "64") (name "VSS") (class "Default")
      (node (ref "C1") (pin "2") (pinfunction "2_2") (pintype "passive"))
      (node (ref "C2") (pin "-") (pinfunction "-_-") (pintype "passive"))
      (node (ref "C3") (pin "2") (pinfunction "2_2") (pintype "passive"))
      (node (ref "C4") (pin "2") (pinfunction "2_2") (pintype "passive"))
      (node (ref "C5") (pin "2") (pinfunction "2_2") (pintype "passive"))
      (node (ref "C6") (pin "-") (pinfunction "-_-") (pintype "passive"))
      (node (ref "C7") (pin "1") (pinfunction "1_1") (pintype "passive"))
      (node (ref "C8") (pin "-") (pinfunction "-_-") (pintype "passive"))
      (node (ref "CON1") (pin "3") (pinfunction "3_3") (pintype "passive"))
      (node (ref "CON1") (pin "4") (pinfunction "4_4") (pintype "passive"))
      (node (ref "D3") (pin "A") (pinfunction "A_A") (pintype "passive"))
      (node (ref "D4") (pin "A") (pinfunction "A_A") (pintype "passive"))
      (node (ref "D5") (pin "A") (pinfunction "A_A") (pintype "passive"))
      (node (ref "Q1") (pin "1") (pinfunction "S_1") (pintype "passive"))
      (node (ref "Q2") (pin "1") (pinfunction "S_1") (pintype "passive"))
      (node (ref "Q3") (pin "1") (pinfunction "S_1") (pintype "passive"))
      (node (ref "Q4") (pin "1") (pinfunction "S_1") (pintype "passive"))
      (node (ref "Q5") (pin "1") (pinfunction "S_1") (pintype "passive"))
      (node (ref "R2") (pin "1") (pinfunction "1_1") (pintype "passive"))
      (node (ref "R7") (pin "1") (pinfunction "1_1") (pintype "passive"))
      (node (ref "SW2") (pin "3") (pinfunction "3_3") (pintype "passive"))
      (node (ref "SW2") (pin "4") (pinfunction "4_4") (pintype "passive"))
      (node (ref "U1") (pin "2") (pinfunction "GND_2") (pintype "passive"))
    )
    (net (code "65") (name "unconnected-(CON1-Pad8)") (class "Default")
      (node (ref "CON1") (pin "8") (pinfunction "8_8") (pintype "passive"))
    )
    (net (code "66") (name "unconnected-(SW1-S-Pad3)") (class "Default")
      (node (ref "SW1") (pin "3") (pinfunction "S_3") (pintype "passive"))
    )
  )
)
